# core-ol.net
KiCad netlist of a schematic drawn in EAGLE
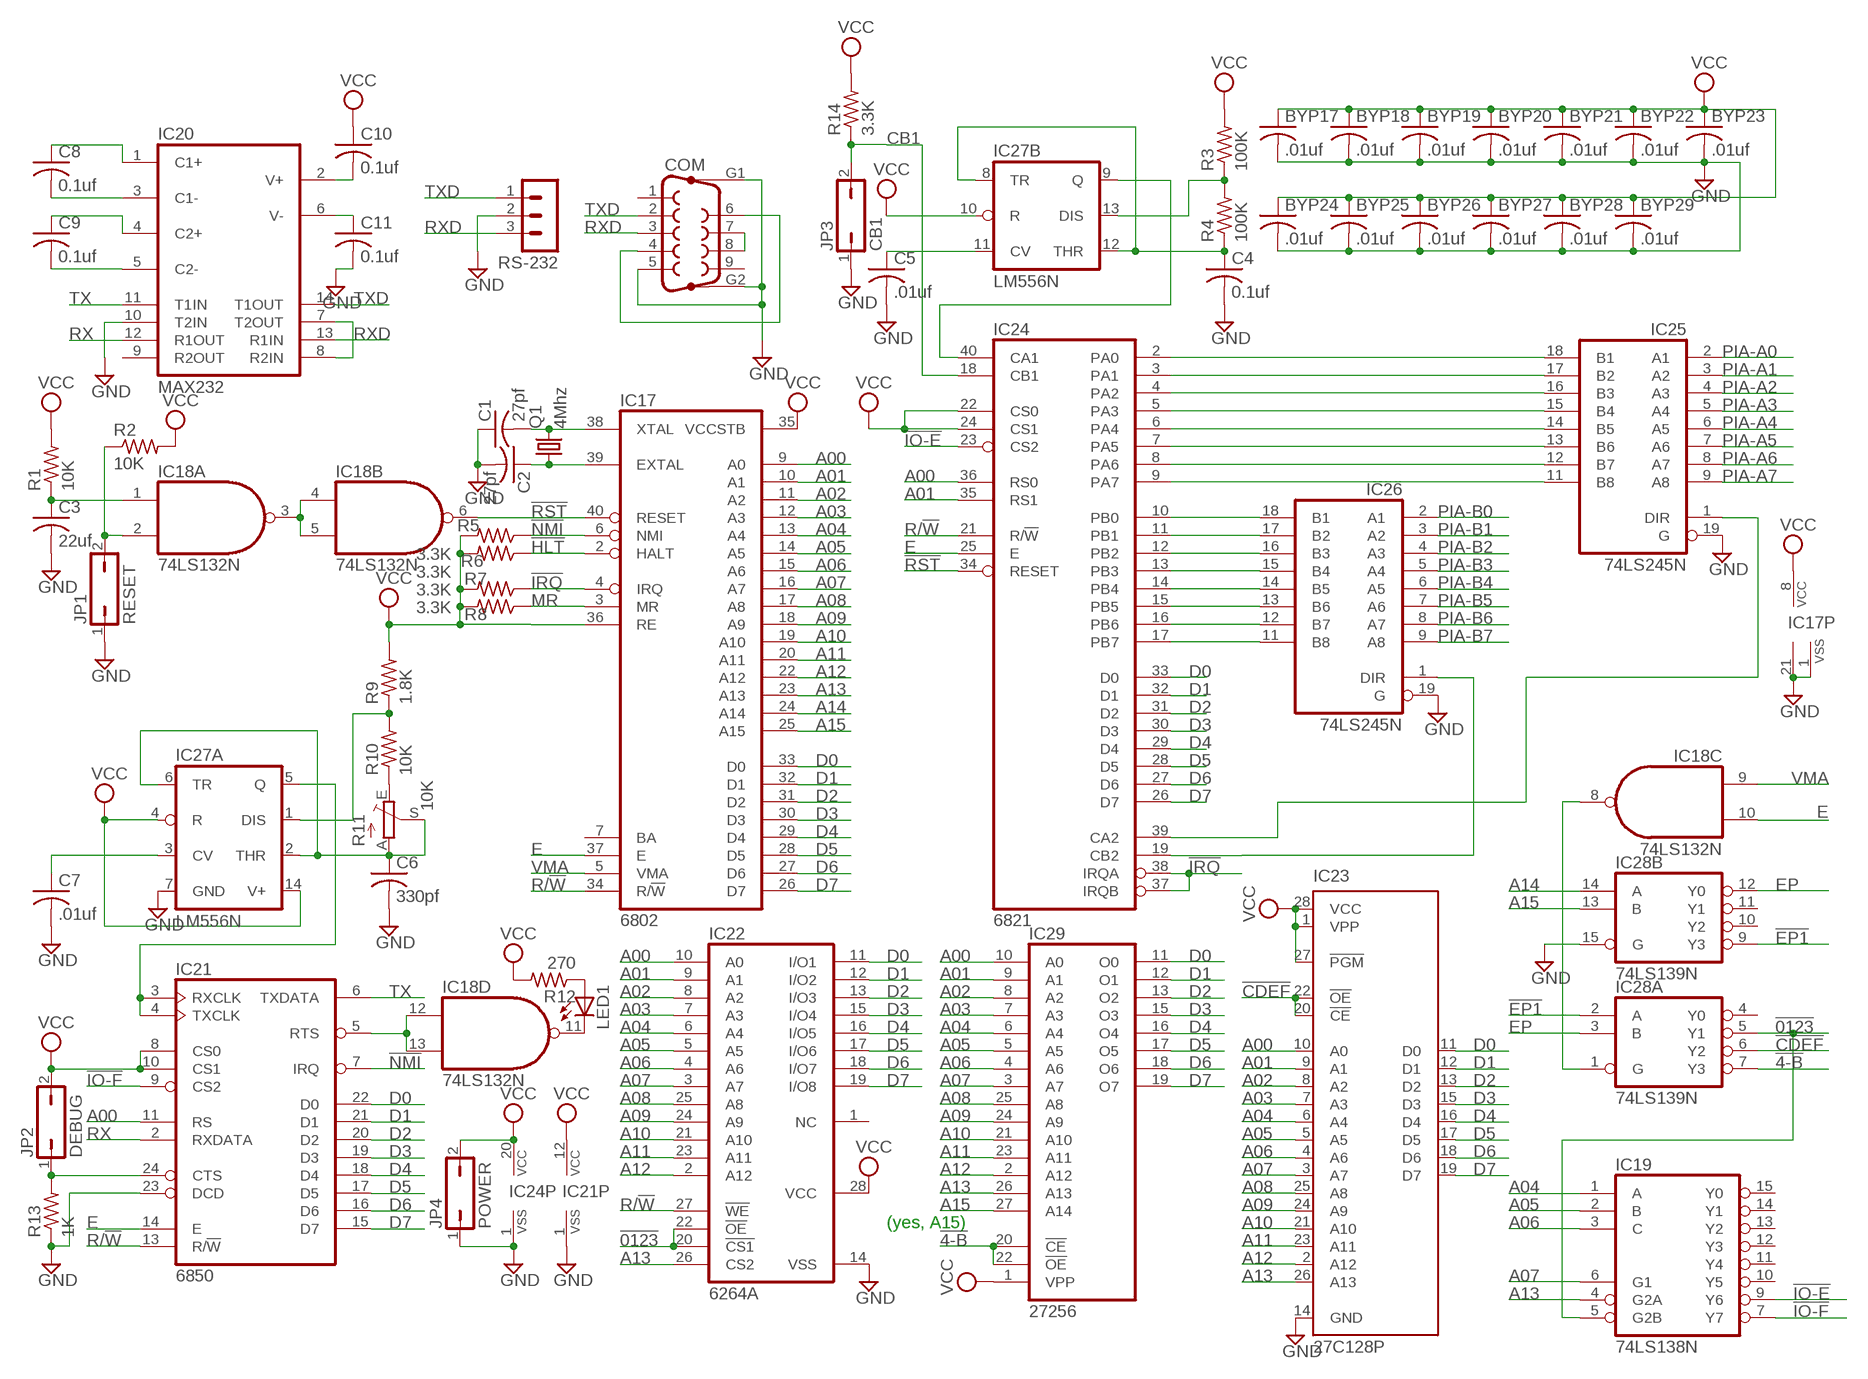
[diagram p0: schematic, sheet 1]
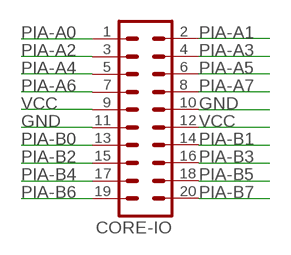
[diagram p1: schematic, sheet 2]

(export (version "E")
  (design (tool "Eeschema 10.0.6"))
  (components
    (comp (ref "BYP17")
      (value ".01uf")
      (footprint "eagle-import:C050-025X075")
      (libsource (lib "eagle-import") (part "C-US050-025X075"))
    )
    (comp (ref "BYP18")
      (value ".01uf")
      (footprint "eagle-import:C050-025X075")
      (libsource (lib "eagle-import") (part "C-US050-025X075"))
    )
    (comp (ref "BYP19")
      (value ".01uf")
      (footprint "eagle-import:C050-025X075")
      (libsource (lib "eagle-import") (part "C-US050-025X075"))
    )
    (comp (ref "BYP20")
      (value ".01uf")
      (footprint "eagle-import:C050-025X075")
      (libsource (lib "eagle-import") (part "C-US050-025X075"))
    )
    (comp (ref "BYP21")
      (value ".01uf")
      (footprint "eagle-import:C050-025X075")
      (libsource (lib "eagle-import") (part "C-US050-025X075"))
    )
    (comp (ref "BYP22")
      (value ".01uf")
      (footprint "eagle-import:C050-025X075")
      (libsource (lib "eagle-import") (part "C-US050-025X075"))
    )
    (comp (ref "BYP23")
      (value ".01uf")
      (footprint "eagle-import:C050-025X075")
      (libsource (lib "eagle-import") (part "C-US050-025X075"))
    )
    (comp (ref "BYP24")
      (value ".01uf")
      (footprint "eagle-import:C050-025X075")
      (libsource (lib "eagle-import") (part "C-US050-025X075"))
    )
    (comp (ref "BYP25")
      (value ".01uf")
      (footprint "eagle-import:C050-025X075")
      (libsource (lib "eagle-import") (part "C-US050-025X075"))
    )
    (comp (ref "BYP26")
      (value ".01uf")
      (footprint "eagle-import:C050-025X075")
      (libsource (lib "eagle-import") (part "C-US050-025X075"))
    )
    (comp (ref "BYP27")
      (value ".01uf")
      (footprint "eagle-import:C050-025X075")
      (libsource (lib "eagle-import") (part "C-US050-025X075"))
    )
    (comp (ref "BYP28")
      (value ".01uf")
      (footprint "eagle-import:C050-025X075")
      (libsource (lib "eagle-import") (part "C-US050-025X075"))
    )
    (comp (ref "BYP29")
      (value ".01uf")
      (footprint "eagle-import:C050-025X075")
      (libsource (lib "eagle-import") (part "C-US050-025X075"))
    )
    (comp (ref "C1")
      (value "27pf")
      (footprint "eagle-import:C050-025X075")
      (libsource (lib "eagle-import") (part "C-US050-025X075"))
    )
    (comp (ref "C2")
      (value "27pf")
      (footprint "eagle-import:C050-025X075")
      (libsource (lib "eagle-import") (part "C-US050-025X075"))
    )
    (comp (ref "C3")
      (value "22uf")
      (footprint "eagle-import:C102-043X133")
      (libsource (lib "eagle-import") (part "C-US102-043X133"))
    )
    (comp (ref "C4")
      (value "0.1uf")
      (footprint "eagle-import:C050-025X075")
      (libsource (lib "eagle-import") (part "C-US050-025X075"))
    )
    (comp (ref "C5")
      (value ".01uf")
      (footprint "eagle-import:C050-025X075")
      (libsource (lib "eagle-import") (part "C-US050-025X075"))
    )
    (comp (ref "C6")
      (value "330pf")
      (footprint "eagle-import:C050-025X075")
      (libsource (lib "eagle-import") (part "C-US050-025X075"))
    )
    (comp (ref "C7")
      (value ".01uf")
      (footprint "eagle-import:C050-025X075")
      (libsource (lib "eagle-import") (part "C-US050-025X075"))
    )
    (comp (ref "C8")
      (value "0.1uf")
      (footprint "eagle-import:C050-025X075")
      (libsource (lib "eagle-import") (part "C-US050-025X075"))
    )
    (comp (ref "C9")
      (value "0.1uf")
      (footprint "eagle-import:C050-025X075")
      (libsource (lib "eagle-import") (part "C-US050-025X075"))
    )
    (comp (ref "C10")
      (value "0.1uf")
      (footprint "eagle-import:C050-025X075")
      (libsource (lib "eagle-import") (part "C-US050-025X075"))
    )
    (comp (ref "C11")
      (value "0.1uf")
      (footprint "eagle-import:C050-025X075")
      (libsource (lib "eagle-import") (part "C-US050-025X075"))
    )
    (comp (ref "COM")
      (value "F09HP")
      (footprint "eagle-import:F09HP")
      (libsource (lib "eagle-import") (part "F09HP"))
    )
    (comp (ref "IC17")
      (value "6802")
      (footprint "eagle-import:DIL40")
      (libsource (lib "eagle-import") (part "6802"))
    )
    (comp (ref "IC18")
      (value "74LS132N")
      (footprint "eagle-import:DIL14")
      (libsource (lib "eagle-import") (part "7400NLS"))
    )
    (comp (ref "IC19")
      (value "74LS138N")
      (footprint "eagle-import:DIL16")
      (libsource (lib "eagle-import") (part "74138NLS"))
    )
    (comp (ref "IC20")
      (value "MAX232")
      (footprint "eagle-import:DIL16")
      (fields (field (name "MF") "MAXIM") (field (name "MPN") "MAX232ACPE+"))
      (libsource (lib "eagle-import") (part "MAX232"))
    )
    (comp (ref "IC21")
      (value "6850")
      (footprint "eagle-import:DIL24")
      (fields (field (name "MF") "NTE ELECTRONICS") (field (name "MPN") "NTE6850"))
      (libsource (lib "eagle-import") (part "6850"))
    )
    (comp (ref "IC22")
      (value "6264A")
      (footprint "eagle-import:DIL28-6")
      (libsource (lib "eagle-import") (part "6264A"))
    )
    (comp (ref "IC23")
      (value "27C128P")
      (footprint "eagle-import:DIL28-6")
      (libsource (lib "eagle-import") (part "27128PC"))
    )
    (comp (ref "IC24")
      (value "6821")
      (footprint "eagle-import:DIL40")
      (fields (field (name "MF") "NTE ELECTRONICS") (field (name "MPN") "NTE6821"))
      (libsource (lib "eagle-import") (part "6821"))
    )
    (comp (ref "IC25")
      (value "74LS245N")
      (footprint "eagle-import:DIL20")
      (libsource (lib "eagle-import") (part "74245NLS"))
    )
    (comp (ref "IC26")
      (value "74LS245N")
      (footprint "eagle-import:DIL20")
      (libsource (lib "eagle-import") (part "74245NLS"))
    )
    (comp (ref "IC27")
      (value "LM556N")
      (footprint "eagle-import:DIL14")
      (libsource (lib "eagle-import") (part "556NLM"))
    )
    (comp (ref "IC28")
      (value "74LS139N")
      (footprint "eagle-import:DIL16")
      (libsource (lib "eagle-import") (part "74139NLS"))
    )
    (comp (ref "IC29")
      (value "27256")
      (footprint "eagle-import:DIL28")
      (libsource (lib "eagle-import") (part "27256"))
    )
    (comp (ref "JP1")
      (value "RESET")
      (footprint "eagle-import:JP1")
      (libsource (lib "eagle-import") (part "JP1Q"))
    )
    (comp (ref "JP2")
      (value "DEBUG")
      (footprint "eagle-import:JP1")
      (libsource (lib "eagle-import") (part "JP1Q"))
    )
    (comp (ref "JP3")
      (value "CB1")
      (footprint "eagle-import:JP1")
      (libsource (lib "eagle-import") (part "JP1Q"))
    )
    (comp (ref "JP4")
      (value "POWER")
      (footprint "eagle-import:JP1")
      (libsource (lib "eagle-import") (part "JP1Q"))
    )
    (comp (ref "LED1")
      (value "LED3MM")
      (footprint "eagle-import:LED3MM")
      (libsource (lib "eagle-import") (part "LED3MM"))
    )
    (comp (ref "Q1")
      (value "4Mhz")
      (footprint "eagle-import:HC18U-V")
      (libsource (lib "eagle-import") (part "CRYSTALHC18U-V"))
    )
    (comp (ref "R1")
      (value "10K")
      (footprint "eagle-import:0207_7")
      (libsource (lib "eagle-import") (part "R-US_0207/7"))
    )
    (comp (ref "R2")
      (value "10K")
      (footprint "eagle-import:0207_7")
      (libsource (lib "eagle-import") (part "R-US_0207/7"))
    )
    (comp (ref "R3")
      (value "100K")
      (footprint "eagle-import:0207_7")
      (libsource (lib "eagle-import") (part "R-US_0207/7"))
    )
    (comp (ref "R4")
      (value "100K")
      (footprint "eagle-import:0207_7")
      (libsource (lib "eagle-import") (part "R-US_0207/7"))
    )
    (comp (ref "R5")
      (value "3.3K")
      (footprint "eagle-import:0207_7")
      (libsource (lib "eagle-import") (part "R-US_0207/7"))
    )
    (comp (ref "R6")
      (value "3.3K")
      (footprint "eagle-import:0207_7")
      (libsource (lib "eagle-import") (part "R-US_0207/7"))
    )
    (comp (ref "R7")
      (value "3.3K")
      (footprint "eagle-import:0207_7")
      (libsource (lib "eagle-import") (part "R-US_0207/7"))
    )
    (comp (ref "R8")
      (value "3.3K")
      (footprint "eagle-import:0207_7")
      (libsource (lib "eagle-import") (part "R-US_0207/7"))
    )
    (comp (ref "R9")
      (value "1.8K")
      (footprint "eagle-import:0207_7")
      (libsource (lib "eagle-import") (part "R-US_0207/7"))
    )
    (comp (ref "R10")
      (value "10K")
      (footprint "eagle-import:0207_7")
      (libsource (lib "eagle-import") (part "R-US_0207/7"))
    )
    (comp (ref "R11")
      (value "10K")
      (footprint "eagle-import:SP19L")
      (libsource (lib "eagle-import") (part "TRIM_EU-B90P"))
    )
    (comp (ref "R12")
      (value "270")
      (footprint "eagle-import:0207_7")
      (libsource (lib "eagle-import") (part "R-US_0207/7"))
    )
    (comp (ref "R13")
      (value "1K")
      (footprint "eagle-import:0207_7")
      (libsource (lib "eagle-import") (part "R-US_0207/7"))
    )
    (comp (ref "R14")
      (value "3.3K")
      (footprint "eagle-import:0207_7")
      (libsource (lib "eagle-import") (part "R-US_0207/7"))
    )
    (comp (ref "RS-232")
      (value "MA03-1")
      (footprint "eagle-import:MA03-1")
      (libsource (lib "eagle-import") (part "MA03-1"))
    )
    (comp (ref "CORE-IO")
      (value "MA10-2")
      (footprint "eagle-import:MA10-2")
      (libsource (lib "eagle-import") (part "MA10-2"))
    )
  )
  (nets
    (net (code "1") (name "A00") (class "Default")
      (node (ref "IC17") (pin "9") (pinfunction "A0_9") (pintype "output"))
      (node (ref "IC21") (pin "11") (pinfunction "RS_11") (pintype "input"))
      (node (ref "IC22") (pin "10") (pinfunction "A0_10") (pintype "input"))
      (node (ref "IC23") (pin "10") (pinfunction "A0_10") (pintype "input"))
      (node (ref "IC24") (pin "36") (pinfunction "RS0_36") (pintype "input"))
      (node (ref "IC29") (pin "10") (pinfunction "A0_10") (pintype "input"))
    )
    (net (code "2") (name "A01") (class "Default")
      (node (ref "IC17") (pin "10") (pinfunction "A1_10") (pintype "output"))
      (node (ref "IC22") (pin "9") (pinfunction "A1_9") (pintype "input"))
      (node (ref "IC23") (pin "9") (pinfunction "A1_9") (pintype "input"))
      (node (ref "IC24") (pin "35") (pinfunction "RS1_35") (pintype "input"))
      (node (ref "IC29") (pin "9") (pinfunction "A1_9") (pintype "input"))
    )
    (net (code "3") (name "A02") (class "Default")
      (node (ref "IC17") (pin "11") (pinfunction "A2_11") (pintype "output"))
      (node (ref "IC22") (pin "8") (pinfunction "A2_8") (pintype "input"))
      (node (ref "IC23") (pin "8") (pinfunction "A2_8") (pintype "input"))
      (node (ref "IC29") (pin "8") (pinfunction "A2_8") (pintype "input"))
    )
    (net (code "4") (name "A03") (class "Default")
      (node (ref "IC17") (pin "12") (pinfunction "A3_12") (pintype "output"))
      (node (ref "IC22") (pin "7") (pinfunction "A3_7") (pintype "input"))
      (node (ref "IC23") (pin "7") (pinfunction "A3_7") (pintype "input"))
      (node (ref "IC29") (pin "7") (pinfunction "A3_7") (pintype "input"))
    )
    (net (code "5") (name "A04") (class "Default")
      (node (ref "IC17") (pin "13") (pinfunction "A4_13") (pintype "output"))
      (node (ref "IC19") (pin "1") (pinfunction "A_1") (pintype "input"))
      (node (ref "IC22") (pin "6") (pinfunction "A4_6") (pintype "input"))
      (node (ref "IC23") (pin "6") (pinfunction "A4_6") (pintype "input"))
      (node (ref "IC29") (pin "6") (pinfunction "A4_6") (pintype "input"))
    )
    (net (code "6") (name "A05") (class "Default")
      (node (ref "IC17") (pin "14") (pinfunction "A5_14") (pintype "output"))
      (node (ref "IC19") (pin "2") (pinfunction "B_2") (pintype "input"))
      (node (ref "IC22") (pin "5") (pinfunction "A5_5") (pintype "input"))
      (node (ref "IC23") (pin "5") (pinfunction "A5_5") (pintype "input"))
      (node (ref "IC29") (pin "5") (pinfunction "A5_5") (pintype "input"))
    )
    (net (code "7") (name "A06") (class "Default")
      (node (ref "IC17") (pin "15") (pinfunction "A6_15") (pintype "output"))
      (node (ref "IC19") (pin "3") (pinfunction "C_3") (pintype "input"))
      (node (ref "IC22") (pin "4") (pinfunction "A6_4") (pintype "input"))
      (node (ref "IC23") (pin "4") (pinfunction "A6_4") (pintype "input"))
      (node (ref "IC29") (pin "4") (pinfunction "A6_4") (pintype "input"))
    )
    (net (code "8") (name "A07") (class "Default")
      (node (ref "IC17") (pin "16") (pinfunction "A7_16") (pintype "output"))
      (node (ref "IC19") (pin "6") (pinfunction "G1_6") (pintype "input"))
      (node (ref "IC22") (pin "3") (pinfunction "A7_3") (pintype "input"))
      (node (ref "IC23") (pin "3") (pinfunction "A7_3") (pintype "input"))
      (node (ref "IC29") (pin "3") (pinfunction "A7_3") (pintype "input"))
    )
    (net (code "9") (name "A08") (class "Default")
      (node (ref "IC17") (pin "17") (pinfunction "A8_17") (pintype "output"))
      (node (ref "IC22") (pin "25") (pinfunction "A8_25") (pintype "input"))
      (node (ref "IC23") (pin "25") (pinfunction "A8_25") (pintype "input"))
      (node (ref "IC29") (pin "25") (pinfunction "A8_25") (pintype "input"))
    )
    (net (code "10") (name "A09") (class "Default")
      (node (ref "IC17") (pin "18") (pinfunction "A9_18") (pintype "output"))
      (node (ref "IC22") (pin "24") (pinfunction "A9_24") (pintype "input"))
      (node (ref "IC23") (pin "24") (pinfunction "A9_24") (pintype "input"))
      (node (ref "IC29") (pin "24") (pinfunction "A9_24") (pintype "input"))
    )
    (net (code "11") (name "A10") (class "Default")
      (node (ref "IC17") (pin "19") (pinfunction "A10_19") (pintype "output"))
      (node (ref "IC22") (pin "21") (pinfunction "A10_21") (pintype "input"))
      (node (ref "IC23") (pin "21") (pinfunction "A10_21") (pintype "input"))
      (node (ref "IC29") (pin "21") (pinfunction "A10_21") (pintype "input"))
    )
    (net (code "12") (name "A11") (class "Default")
      (node (ref "IC17") (pin "20") (pinfunction "A11_20") (pintype "output"))
      (node (ref "IC22") (pin "23") (pinfunction "A11_23") (pintype "input"))
      (node (ref "IC23") (pin "23") (pinfunction "A11_23") (pintype "input"))
      (node (ref "IC29") (pin "23") (pinfunction "A11_23") (pintype "input"))
    )
    (net (code "13") (name "A12") (class "Default")
      (node (ref "IC17") (pin "22") (pinfunction "A12_22") (pintype "output"))
      (node (ref "IC22") (pin "2") (pinfunction "A12_2") (pintype "input"))
      (node (ref "IC23") (pin "2") (pinfunction "A12_2") (pintype "input"))
      (node (ref "IC29") (pin "2") (pinfunction "A12_2") (pintype "input"))
    )
    (net (code "14") (name "A13") (class "Default")
      (node (ref "IC17") (pin "23") (pinfunction "A13_23") (pintype "output"))
      (node (ref "IC19") (pin "4") (pinfunction "G2A_4") (pintype "input"))
      (node (ref "IC22") (pin "26") (pinfunction "CS2_26") (pintype "input"))
      (node (ref "IC23") (pin "26") (pinfunction "A13_26") (pintype "input"))
      (node (ref "IC29") (pin "26") (pinfunction "A13_26") (pintype "input"))
    )
    (net (code "15") (name "A14") (class "Default")
      (node (ref "IC17") (pin "24") (pinfunction "A14_24") (pintype "output"))
      (node (ref "IC28") (pin "14") (pinfunction "A_14") (pintype "input"))
    )
    (net (code "16") (name "A15") (class "Default")
      (node (ref "IC17") (pin "25") (pinfunction "A15_25") (pintype "output"))
      (node (ref "IC28") (pin "13") (pinfunction "B_13") (pintype "input"))
      (node (ref "IC29") (pin "27") (pinfunction "A14_27") (pintype "input"))
    )
    (net (code "17") (name "CB1") (class "Default")
      (node (ref "IC24") (pin "18") (pinfunction "CB1_18") (pintype "input"))
      (node (ref "JP3") (pin "2") (pinfunction "2_2") (pintype "passive"))
      (node (ref "R14") (pin "1") (pinfunction "1_1") (pintype "passive"))
    )
    (net (code "18") (name "D0") (class "Default")
      (node (ref "IC17") (pin "33") (pinfunction "D0_33") (pintype "bidirectional"))
      (node (ref "IC21") (pin "22") (pinfunction "D0_22") (pintype "bidirectional"))
      (node (ref "IC22") (pin "11") (pinfunction "I/O1_11") (pintype "bidirectional"))
      (node (ref "IC23") (pin "11") (pinfunction "D0_11") (pintype "tri_state"))
      (node (ref "IC24") (pin "33") (pinfunction "D0_33") (pintype "bidirectional"))
      (node (ref "IC29") (pin "11") (pinfunction "O0_11") (pintype "tri_state"))
    )
    (net (code "19") (name "D1") (class "Default")
      (node (ref "IC17") (pin "32") (pinfunction "D1_32") (pintype "bidirectional"))
      (node (ref "IC21") (pin "21") (pinfunction "D1_21") (pintype "bidirectional"))
      (node (ref "IC22") (pin "12") (pinfunction "I/O2_12") (pintype "bidirectional"))
      (node (ref "IC23") (pin "12") (pinfunction "D1_12") (pintype "tri_state"))
      (node (ref "IC24") (pin "32") (pinfunction "D1_32") (pintype "bidirectional"))
      (node (ref "IC29") (pin "12") (pinfunction "O1_12") (pintype "tri_state"))
    )
    (net (code "20") (name "D2") (class "Default")
      (node (ref "IC17") (pin "31") (pinfunction "D2_31") (pintype "bidirectional"))
      (node (ref "IC21") (pin "20") (pinfunction "D2_20") (pintype "bidirectional"))
      (node (ref "IC22") (pin "13") (pinfunction "I/O3_13") (pintype "bidirectional"))
      (node (ref "IC23") (pin "13") (pinfunction "D2_13") (pintype "tri_state"))
      (node (ref "IC24") (pin "31") (pinfunction "D2_31") (pintype "bidirectional"))
      (node (ref "IC29") (pin "13") (pinfunction "O2_13") (pintype "tri_state"))
    )
    (net (code "21") (name "D3") (class "Default")
      (node (ref "IC17") (pin "30") (pinfunction "D3_30") (pintype "bidirectional"))
      (node (ref "IC21") (pin "19") (pinfunction "D3_19") (pintype "bidirectional"))
      (node (ref "IC22") (pin "15") (pinfunction "I/O4_15") (pintype "bidirectional"))
      (node (ref "IC23") (pin "15") (pinfunction "D3_15") (pintype "tri_state"))
      (node (ref "IC24") (pin "30") (pinfunction "D3_30") (pintype "bidirectional"))
      (node (ref "IC29") (pin "15") (pinfunction "O3_15") (pintype "tri_state"))
    )
    (net (code "22") (name "D4") (class "Default")
      (node (ref "IC17") (pin "29") (pinfunction "D4_29") (pintype "bidirectional"))
      (node (ref "IC21") (pin "18") (pinfunction "D4_18") (pintype "bidirectional"))
      (node (ref "IC22") (pin "16") (pinfunction "I/O5_16") (pintype "bidirectional"))
      (node (ref "IC23") (pin "16") (pinfunction "D4_16") (pintype "tri_state"))
      (node (ref "IC24") (pin "29") (pinfunction "D4_29") (pintype "bidirectional"))
      (node (ref "IC29") (pin "16") (pinfunction "O4_16") (pintype "tri_state"))
    )
    (net (code "23") (name "D5") (class "Default")
      (node (ref "IC17") (pin "28") (pinfunction "D5_28") (pintype "bidirectional"))
      (node (ref "IC21") (pin "17") (pinfunction "D5_17") (pintype "bidirectional"))
      (node (ref "IC22") (pin "17") (pinfunction "I/O6_17") (pintype "bidirectional"))
      (node (ref "IC23") (pin "17") (pinfunction "D5_17") (pintype "tri_state"))
      (node (ref "IC24") (pin "28") (pinfunction "D5_28") (pintype "bidirectional"))
      (node (ref "IC29") (pin "17") (pinfunction "O5_17") (pintype "tri_state"))
    )
    (net (code "24") (name "D6") (class "Default")
      (node (ref "IC17") (pin "27") (pinfunction "D6_27") (pintype "bidirectional"))
      (node (ref "IC21") (pin "16") (pinfunction "D6_16") (pintype "bidirectional"))
      (node (ref "IC22") (pin "18") (pinfunction "I/O7_18") (pintype "bidirectional"))
      (node (ref "IC23") (pin "18") (pinfunction "D6_18") (pintype "tri_state"))
      (node (ref "IC24") (pin "27") (pinfunction "D6_27") (pintype "bidirectional"))
      (node (ref "IC29") (pin "18") (pinfunction "O6_18") (pintype "tri_state"))
    )
    (net (code "25") (name "D7") (class "Default")
      (node (ref "IC17") (pin "26") (pinfunction "D7_26") (pintype "bidirectional"))
      (node (ref "IC21") (pin "15") (pinfunction "D7_15") (pintype "bidirectional"))
      (node (ref "IC22") (pin "19") (pinfunction "I/O8_19") (pintype "bidirectional"))
      (node (ref "IC23") (pin "19") (pinfunction "D7_19") (pintype "tri_state"))
      (node (ref "IC24") (pin "26") (pinfunction "D7_26") (pintype "bidirectional"))
      (node (ref "IC29") (pin "19") (pinfunction "O7_19") (pintype "tri_state"))
    )
    (net (code "26") (name "E") (class "Default")
      (node (ref "IC17") (pin "37") (pinfunction "E_37") (pintype "output"))
      (node (ref "IC18") (pin "10") (pinfunction "I1_10") (pintype "input"))
      (node (ref "IC21") (pin "14") (pinfunction "E_14") (pintype "input"))
      (node (ref "IC24") (pin "25") (pinfunction "E_25") (pintype "input"))
    )
    (net (code "27") (name "EP") (class "Default")
      (node (ref "IC28") (pin "12") (pinfunction "Y0_12") (pintype "output"))
      (node (ref "IC28") (pin "3") (pinfunction "B_3") (pintype "input"))
    )
    (net (code "28") (name "GND") (class "Default")
      (node (ref "BYP17") (pin "2") (pinfunction "2_2") (pintype "passive"))
      (node (ref "BYP18") (pin "2") (pinfunction "2_2") (pintype "passive"))
      (node (ref "BYP19") (pin "2") (pinfunction "2_2") (pintype "passive"))
      (node (ref "BYP20") (pin "2") (pinfunction "2_2") (pintype "passive"))
      (node (ref "BYP21") (pin "2") (pinfunction "2_2") (pintype "passive"))
      (node (ref "BYP22") (pin "2") (pinfunction "2_2") (pintype "passive"))
      (node (ref "BYP23") (pin "2") (pinfunction "2_2") (pintype "passive"))
      (node (ref "BYP24") (pin "2") (pinfunction "2_2") (pintype "passive"))
      (node (ref "BYP25") (pin "2") (pinfunction "2_2") (pintype "passive"))
      (node (ref "BYP26") (pin "2") (pinfunction "2_2") (pintype "passive"))
      (node (ref "BYP27") (pin "2") (pinfunction "2_2") (pintype "passive"))
      (node (ref "BYP28") (pin "2") (pinfunction "2_2") (pintype "passive"))
      (node (ref "BYP29") (pin "2") (pinfunction "2_2") (pintype "passive"))
      (node (ref "C1") (pin "1") (pinfunction "1_1") (pintype "passive"))
      (node (ref "C11") (pin "2") (pinfunction "2_2") (pintype "passive"))
      (node (ref "C2") (pin "2") (pinfunction "2_2") (pintype "passive"))
      (node (ref "C3") (pin "2") (pinfunction "2_2") (pintype "passive"))
      (node (ref "C4") (pin "2") (pinfunction "2_2") (pintype "passive"))
      (node (ref "C5") (pin "2") (pinfunction "2_2") (pintype "passive"))
      (node (ref "C6") (pin "2") (pinfunction "2_2") (pintype "passive"))
      (node (ref "C7") (pin "2") (pinfunction "2_2") (pintype "passive"))
      (node (ref "COM") (pin "5") (pinfunction "5_5") (pintype "passive"))
      (node (ref "COM") (pin "G1") (pinfunction "G1_G1") (pintype "passive"))
      (node (ref "COM") (pin "G2") (pinfunction "G2_G2") (pintype "passive"))
      (node (ref "CORE-IO") (pin "10") (pinfunction "10_10") (pintype "passive"))
      (node (ref "CORE-IO") (pin "11") (pinfunction "11_11") (pintype "passive"))
      (node (ref "IC17") (pin "1") (pinfunction "VSS_1") (pintype "power_in"))
      (node (ref "IC17") (pin "21") (pinfunction "VSS_21") (pintype "power_in"))
      (node (ref "IC20") (pin "10") (pinfunction "T2IN_10") (pintype "input"))
      (node (ref "IC21") (pin "1") (pinfunction "VSS_1") (pintype "power_in"))
      (node (ref "IC21") (pin "23") (pinfunction "DCD_23") (pintype "input"))
      (node (ref "IC22") (pin "14") (pinfunction "VSS_14") (pintype "power_in"))
      (node (ref "IC23") (pin "14") (pinfunction "GND_14") (pintype "power_in"))
      (node (ref "IC24") (pin "1") (pinfunction "VSS_1") (pintype "power_in"))
      (node (ref "IC25") (pin "19") (pinfunction "G_19") (pintype "input"))
      (node (ref "IC26") (pin "19") (pinfunction "G_19") (pintype "input"))
      (node (ref "IC27") (pin "7") (pinfunction "GND_7") (pintype "power_in"))
      (node (ref "IC28") (pin "15") (pinfunction "G_15") (pintype "input"))
      (node (ref "JP1") (pin "1") (pinfunction "1_1") (pintype "passive"))
      (node (ref "JP3") (pin "1") (pinfunction "1_1") (pintype "passive"))
      (node (ref "JP4") (pin "1") (pinfunction "1_1") (pintype "passive"))
      (node (ref "R13") (pin "1") (pinfunction "1_1") (pintype "passive"))
      (node (ref "RS-232") (pin "2") (pinfunction "2_2") (pintype "passive"))
    )
    (net (code "29") (name "MR") (class "Default")
      (node (ref "IC17") (pin "3") (pinfunction "MR_3") (pintype "input"))
      (node (ref "R8") (pin "1") (pinfunction "1_1") (pintype "passive"))
    )
    (net (code "30") (name "Net-(COM-Pad4)") (class "Default")
      (node (ref "COM") (pin "4") (pinfunction "4_4") (pintype "passive"))
      (node (ref "COM") (pin "6") (pinfunction "6_6") (pintype "passive"))
    )
    (net (code "31") (name "Net-(COM-Pad7)") (class "Default")
      (node (ref "COM") (pin "7") (pinfunction "7_7") (pintype "passive"))
      (node (ref "COM") (pin "8") (pinfunction "8_8") (pintype "passive"))
    )
    (net (code "32") (name "Net-(IC17A-EXTAL)") (class "Default")
      (node (ref "C2") (pin "1") (pinfunction "1_1") (pintype "passive"))
      (node (ref "IC17") (pin "39") (pinfunction "EXTAL_39") (pintype "input"))
      (node (ref "Q1") (pin "1") (pinfunction "1_1") (pintype "passive"))
    )
    (net (code "33") (name "Net-(IC17A-XTAL)") (class "Default")
      (node (ref "C1") (pin "2") (pinfunction "2_2") (pintype "passive"))
      (node (ref "IC17") (pin "38") (pinfunction "XTAL_38") (pintype "input"))
      (node (ref "Q1") (pin "2") (pinfunction "2_2") (pintype "passive"))
    )
    (net (code "34") (name "Net-(IC18A-I0)") (class "Default")
      (node (ref "C3") (pin "1") (pinfunction "1_1") (pintype "passive"))
      (node (ref "IC18") (pin "1") (pinfunction "I0_1") (pintype "input"))
      (node (ref "R1") (pin "1") (pinfunction "1_1") (pintype "passive"))
    )
    (net (code "35") (name "Net-(IC18A-I1)") (class "Default")
      (node (ref "IC18") (pin "2") (pinfunction "I1_2") (pintype "input"))
      (node (ref "JP1") (pin "2") (pinfunction "2_2") (pintype "passive"))
      (node (ref "R2") (pin "1") (pinfunction "1_1") (pintype "passive"))
    )
    (net (code "36") (name "Net-(IC18A-O)") (class "Default")
      (node (ref "IC18") (pin "3") (pinfunction "O_3") (pintype "output"))
      (node (ref "IC18") (pin "4") (pinfunction "I0_4") (pintype "input"))
      (node (ref "IC18") (pin "5") (pinfunction "I1_5") (pintype "input"))
    )
    (net (code "37") (name "Net-(IC18C-O)") (class "Default")
      (node (ref "IC18") (pin "8") (pinfunction "O_8") (pintype "output"))
      (node (ref "IC28") (pin "1") (pinfunction "G_1") (pintype "input"))
    )
    (net (code "38") (name "Net-(IC18D-I0)") (class "Default")
      (node (ref "IC18") (pin "12") (pinfunction "I0_12") (pintype "input"))
      (node (ref "IC18") (pin "13") (pinfunction "I1_13") (pintype "input"))
      (node (ref "IC21") (pin "5") (pinfunction "RTS_5") (pintype "output"))
    )
    (net (code "39") (name "Net-(IC18D-O)") (class "Default")
      (node (ref "IC18") (pin "11") (pinfunction "O_11") (pintype "output"))
      (node (ref "LED1") (pin "K") (pinfunction "C_K") (pintype "passive"))
    )
    (net (code "40") (name "Net-(IC20A-C1+)") (class "Default")
      (node (ref "C8") (pin "1") (pinfunction "1_1") (pintype "passive"))
      (node (ref "IC20") (pin "1") (pinfunction "C1+_1") (pintype "bidirectional"))
    )
    (net (code "41") (name "Net-(IC20A-C1-)") (class "Default")
      (node (ref "C8") (pin "2") (pinfunction "2_2") (pintype "passive"))
      (node (ref "IC20") (pin "3") (pinfunction "C1-_3") (pintype "bidirectional"))
    )
    (net (code "42") (name "Net-(IC20A-C2+)") (class "Default")
      (node (ref "C9") (pin "1") (pinfunction "1_1") (pintype "passive"))
      (node (ref "IC20") (pin "4") (pinfunction "C2+_4") (pintype "bidirectional"))
    )
    (net (code "43") (name "Net-(IC20A-C2-)") (class "Default")
      (node (ref "C9") (pin "2") (pinfunction "2_2") (pintype "passive"))
      (node (ref "IC20") (pin "5") (pinfunction "C2-_5") (pintype "bidirectional"))
    )
    (net (code "44") (name "Net-(IC20A-R2IN)") (class "Default")
      (node (ref "IC20") (pin "7") (pinfunction "T2OUT_7") (pintype "output"))
      (node (ref "IC20") (pin "8") (pinfunction "R2IN_8") (pintype "input"))
    )
    (net (code "45") (name "Net-(IC20A-V+)") (class "Default")
      (node (ref "C10") (pin "2") (pinfunction "2_2") (pintype "passive"))
      (node (ref "IC20") (pin "2") (pinfunction "V+_2") (pintype "bidirectional"))
    )
    (net (code "46") (name "Net-(IC20A-V-)") (class "Default")
      (node (ref "C11") (pin "1") (pinfunction "1_1") (pintype "passive"))
      (node (ref "IC20") (pin "6") (pinfunction "V-_6") (pintype "bidirectional"))
    )
    (net (code "47") (name "Net-(IC21A-CTS)") (class "Default")
      (node (ref "IC21") (pin "24") (pinfunction "CTS_24") (pintype "input"))
      (node (ref "JP2") (pin "1") (pinfunction "1_1") (pintype "passive"))
      (node (ref "R13") (pin "2") (pinfunction "2_2") (pintype "passive"))
    )
    (net (code "48") (name "Net-(IC21A-RXCLK)") (class "Default")
      (node (ref "IC21") (pin "3") (pinfunction "RXCLK_3") (pintype "input"))
      (node (ref "IC21") (pin "4") (pinfunction "TXCLK_4") (pintype "input"))
      (node (ref "IC27") (pin "5") (pinfunction "Q_5") (pintype "output"))
    )
    (net (code "49") (name "Net-(IC24A-CA1)") (class "Default")
      (node (ref "IC24") (pin "40") (pinfunction "CA1_40") (pintype "input"))
      (node (ref "IC27") (pin "9") (pinfunction "Q_9") (pintype "output"))
    )
    (net (code "50") (name "Net-(IC24A-CA2)") (class "Default")
      (node (ref "IC24") (pin "39") (pinfunction "CA2_39") (pintype "bidirectional"))
      (node (ref "IC25") (pin "1") (pinfunction "DIR_1") (pintype "input"))
    )
    (net (code "51") (name "Net-(IC24A-CB2)") (class "Default")
      (node (ref "IC24") (pin "19") (pinfunction "CB2_19") (pintype "bidirectional"))
      (node (ref "IC26") (pin "1") (pinfunction "DIR_1") (pintype "input"))
    )
    (net (code "52") (name "Net-(IC24A-PA0)") (class "Default")
      (node (ref "IC24") (pin "2") (pinfunction "PA0_2") (pintype "bidirectional"))
      (node (ref "IC25") (pin "18") (pinfunction "B1_18") (pintype "bidirectional"))
    )
    (net (code "53") (name "Net-(IC24A-PA1)") (class "Default")
      (node (ref "IC24") (pin "3") (pinfunction "PA1_3") (pintype "bidirectional"))
      (node (ref "IC25") (pin "17") (pinfunction "B2_17") (pintype "bidirectional"))
    )
    (net (code "54") (name "Net-(IC24A-PA2)") (class "Default")
      (node (ref "IC24") (pin "4") (pinfunction "PA2_4") (pintype "bidirectional"))
      (node (ref "IC25") (pin "16") (pinfunction "B3_16") (pintype "bidirectional"))
    )
    (net (code "55") (name "Net-(IC24A-PA3)") (class "Default")
      (node (ref "IC24") (pin "5") (pinfunction "PA3_5") (pintype "bidirectional"))
      (node (ref "IC25") (pin "15") (pinfunction "B4_15") (pintype "bidirectional"))
    )
    (net (code "56") (name "Net-(IC24A-PA4)") (class "Default")
      (node (ref "IC24") (pin "6") (pinfunction "PA4_6") (pintype "bidirectional"))
      (node (ref "IC25") (pin "14") (pinfunction "B5_14") (pintype "bidirectional"))
    )
    (net (code "57") (name "Net-(IC24A-PA5)") (class "Default")
      (node (ref "IC24") (pin "7") (pinfunction "PA5_7") (pintype "bidirectional"))
      (node (ref "IC25") (pin "13") (pinfunction "B6_13") (pintype "bidirectional"))
    )
    (net (code "58") (name "Net-(IC24A-PA6)") (class "Default")
      (node (ref "IC24") (pin "8") (pinfunction "PA6_8") (pintype "bidirectional"))
      (node (ref "IC25") (pin "12") (pinfunction "B7_12") (pintype "bidirectional"))
    )
    (net (code "59") (name "Net-(IC24A-PA7)") (class "Default")
      (node (ref "IC24") (pin "9") (pinfunction "PA7_9") (pintype "bidirectional"))
      (node (ref "IC25") (pin "11") (pinfunction "B8_11") (pintype "bidirectional"))
    )
    (net (code "60") (name "Net-(IC24A-PB0)") (class "Default")
      (node (ref "IC24") (pin "10") (pinfunction "PB0_10") (pintype "bidirectional"))
      (node (ref "IC26") (pin "18") (pinfunction "B1_18") (pintype "bidirectional"))
    )
    (net (code "61") (name "Net-(IC24A-PB1)") (class "Default")
      (node (ref "IC24") (pin "11") (pinfunction "PB1_11") (pintype "bidirectional"))
      (node (ref "IC26") (pin "17") (pinfunction "B2_17") (pintype "bidirectional"))
    )
    (net (code "62") (name "Net-(IC24A-PB2)") (class "Default")
      (node (ref "IC24") (pin "12") (pinfunction "PB2_12") (pintype "bidirectional"))
      (node (ref "IC26") (pin "16") (pinfunction "B3_16") (pintype "bidirectional"))
    )
    (net (code "63") (name "Net-(IC24A-PB3)") (class "Default")
      (node (ref "IC24") (pin "13") (pinfunction "PB3_13") (pintype "bidirectional"))
      (node (ref "IC26") (pin "15") (pinfunction "B4_15") (pintype "bidirectional"))
    )
    (net (code "64") (name "Net-(IC24A-PB4)") (class "Default")
      (node (ref "IC24") (pin "14") (pinfunction "PB4_14") (pintype "bidirectional"))
      (node (ref "IC26") (pin "14") (pinfunction "B5_14") (pintype "bidirectional"))
    )
    (net (code "65") (name "Net-(IC24A-PB5)") (class "Default")
      (node (ref "IC24") (pin "15") (pinfunction "PB5_15") (pintype "bidirectional"))
      (node (ref "IC26") (pin "13") (pinfunction "B6_13") (pintype "bidirectional"))
    )
    (net (code "66") (name "Net-(IC24A-PB6)") (class "Default")
      (node (ref "IC24") (pin "16") (pinfunction "PB6_16") (pintype "bidirectional"))
      (node (ref "IC26") (pin "12") (pinfunction "B7_12") (pintype "bidirectional"))
    )
    (net (code "67") (name "Net-(IC24A-PB7)") (class "Default")
      (node (ref "IC24") (pin "17") (pinfunction "PB7_17") (pintype "bidirectional"))
      (node (ref "IC26") (pin "11") (pinfunction "B8_11") (pintype "bidirectional"))
    )
    (net (code "68") (name "Net-(IC27A-CV)") (class "Default")
      (node (ref "C7") (pin "1") (pinfunction "1_1") (pintype "passive"))
      (node (ref "IC27") (pin "3") (pinfunction "CV_3") (pintype "input"))
    )
    (net (code "69") (name "Net-(IC27A-DIS)") (class "Default")
      (node (ref "IC27") (pin "1") (pinfunction "DIS_1") (pintype "input"))
      (node (ref "R10") (pin "2") (pinfunction "2_2") (pintype "passive"))
      (node (ref "R9") (pin "1") (pinfunction "1_1") (pintype "passive"))
    )
    (net (code "70") (name "Net-(IC27A-THR)") (class "Default")
      (node (ref "C6") (pin "1") (pinfunction "1_1") (pintype "passive"))
      (node (ref "IC27") (pin "2") (pinfunction "THR_2") (pintype "input"))
      (node (ref "IC27") (pin "6") (pinfunction "TR_6") (pintype "input"))
      (node (ref "R11") (pin "A") (pinfunction "A_A") (pintype "passive"))
      (node (ref "R11") (pin "S") (pinfunction "S_S") (pintype "passive"))
    )
    (net (code "71") (name "Net-(IC27B-CV)") (class "Default")
      (node (ref "C5") (pin "1") (pinfunction "1_1") (pintype "passive"))
      (node (ref "IC27") (pin "11") (pinfunction "CV_11") (pintype "input"))
    )
    (net (code "72") (name "Net-(IC27B-DIS)") (class "Default")
      (node (ref "IC27") (pin "13") (pinfunction "DIS_13") (pintype "input"))
      (node (ref "R3") (pin "1") (pinfunction "1_1") (pintype "passive"))
      (node (ref "R4") (pin "2") (pinfunction "2_2") (pintype "passive"))
    )
    (net (code "73") (name "Net-(IC27B-THR)") (class "Default")
      (node (ref "C4") (pin "1") (pinfunction "1_1") (pintype "passive"))
      (node (ref "IC27") (pin "12") (pinfunction "THR_12") (pintype "input"))
      (node (ref "IC27") (pin "8") (pinfunction "TR_8") (pintype "input"))
      (node (ref "R4") (pin "1") (pinfunction "1_1") (pintype "passive"))
    )
    (net (code "74") (name "Net-(LED1-PadA)") (class "Default")
      (node (ref "LED1") (pin "A") (pinfunction "A_A") (pintype "passive"))
      (node (ref "R12") (pin "1") (pinfunction "1_1") (pintype "passive"))
    )
    (net (code "75") (name "Net-(R10-Pad1)") (class "Default")
      (node (ref "R10") (pin "1") (pinfunction "1_1") (pintype "passive"))
      (node (ref "R11") (pin "E") (pinfunction "E_E") (pintype "passive"))
    )
    (net (code "76") (name "PIA-A0") (class "Default")
      (node (ref "CORE-IO") (pin "1") (pinfunction "1_1") (pintype "passive"))
      (node (ref "IC25") (pin "2") (pinfunction "A1_2") (pintype "bidirectional"))
    )
    (net (code "77") (name "PIA-A1") (class "Default")
      (node (ref "CORE-IO") (pin "2") (pinfunction "2_2") (pintype "passive"))
      (node (ref "IC25") (pin "3") (pinfunction "A2_3") (pintype "bidirectional"))
    )
    (net (code "78") (name "PIA-A2") (class "Default")
      (node (ref "CORE-IO") (pin "3") (pinfunction "3_3") (pintype "passive"))
      (node (ref "IC25") (pin "4") (pinfunction "A3_4") (pintype "bidirectional"))
    )
    (net (code "79") (name "PIA-A3") (class "Default")
      (node (ref "CORE-IO") (pin "4") (pinfunction "4_4") (pintype "passive"))
      (node (ref "IC25") (pin "5") (pinfunction "A4_5") (pintype "bidirectional"))
    )
    (net (code "80") (name "PIA-A4") (class "Default")
      (node (ref "CORE-IO") (pin "5") (pinfunction "5_5") (pintype "passive"))
      (node (ref "IC25") (pin "6") (pinfunction "A5_6") (pintype "bidirectional"))
    )
    (net (code "81") (name "PIA-A5") (class "Default")
      (node (ref "CORE-IO") (pin "6") (pinfunction "6_6") (pintype "passive"))
      (node (ref "IC25") (pin "7") (pinfunction "A6_7") (pintype "bidirectional"))
    )
    (net (code "82") (name "PIA-A6") (class "Default")
      (node (ref "CORE-IO") (pin "7") (pinfunction "7_7") (pintype "passive"))
      (node (ref "IC25") (pin "8") (pinfunction "A7_8") (pintype "bidirectional"))
    )
    (net (code "83") (name "PIA-A7") (class "Default")
      (node (ref "CORE-IO") (pin "8") (pinfunction "8_8") (pintype "passive"))
      (node (ref "IC25") (pin "9") (pinfunction "A8_9") (pintype "bidirectional"))
    )
    (net (code "84") (name "PIA-B0") (class "Default")
      (node (ref "CORE-IO") (pin "13") (pinfunction "13_13") (pintype "passive"))
      (node (ref "IC26") (pin "2") (pinfunction "A1_2") (pintype "bidirectional"))
    )
    (net (code "85") (name "PIA-B1") (class "Default")
      (node (ref "CORE-IO") (pin "14") (pinfunction "14_14") (pintype "passive"))
      (node (ref "IC26") (pin "3") (pinfunction "A2_3") (pintype "bidirectional"))
    )
    (net (code "86") (name "PIA-B2") (class "Default")
      (node (ref "CORE-IO") (pin "15") (pinfunction "15_15") (pintype "passive"))
      (node (ref "IC26") (pin "4") (pinfunction "A3_4") (pintype "bidirectional"))
    )
    (net (code "87") (name "PIA-B3") (class "Default")
      (node (ref "CORE-IO") (pin "16") (pinfunction "16_16") (pintype "passive"))
      (node (ref "IC26") (pin "5") (pinfunction "A4_5") (pintype "bidirectional"))
    )
    (net (code "88") (name "PIA-B4") (class "Default")
      (node (ref "CORE-IO") (pin "17") (pinfunction "17_17") (pintype "passive"))
      (node (ref "IC26") (pin "6") (pinfunction "A5_6") (pintype "bidirectional"))
    )
    (net (code "89") (name "PIA-B5") (class "Default")
      (node (ref "CORE-IO") (pin "18") (pinfunction "18_18") (pintype "passive"))
      (node (ref "IC26") (pin "7") (pinfunction "A6_7") (pintype "bidirectional"))
    )
    (net (code "90") (name "PIA-B6") (class "Default")
      (node (ref "CORE-IO") (pin "19") (pinfunction "19_19") (pintype "passive"))
      (node (ref "IC26") (pin "8") (pinfunction "A7_8") (pintype "bidirectional"))
    )
    (net (code "91") (name "PIA-B7") (class "Default")
      (node (ref "CORE-IO") (pin "20") (pinfunction "20_20") (pintype "passive"))
      (node (ref "IC26") (pin "9") (pinfunction "A8_9") (pintype "bidirectional"))
    )
    (net (code "92") (name "RX") (class "Default")
      (node (ref "IC20") (pin "12") (pinfunction "R1OUT_12") (pintype "output"))
      (node (ref "IC21") (pin "2") (pinfunction "RXDATA_2") (pintype "input"))
    )
    (net (code "93") (name "RXD") (class "Default")
      (node (ref "COM") (pin "3") (pinfunction "3_3") (pintype "passive"))
      (node (ref "IC20") (pin "13") (pinfunction "R1IN_13") (pintype "input"))
      (node (ref "RS-232") (pin "3") (pinfunction "3_3") (pintype "passive"))
    )
    (net (code "94") (name "R{slash}~{W}") (class "Default")
      (node (ref "IC17") (pin "34") (pinfunction "R/~{W}_34") (pintype "output"))
      (node (ref "IC21") (pin "13") (pinfunction "R/~{W}_13") (pintype "input"))
      (node (ref "IC22") (pin "27") (pinfunction "~{WE}_27") (pintype "input"))
      (node (ref "IC24") (pin "21") (pinfunction "R/~{W}_21") (pintype "input"))
    )
    (net (code "95") (name "TX") (class "Default")
      (node (ref "IC20") (pin "11") (pinfunction "T1IN_11") (pintype "input"))
      (node (ref "IC21") (pin "6") (pinfunction "TXDATA_6") (pintype "output"))
    )
    (net (code "96") (name "TXD") (class "Default")
      (node (ref "COM") (pin "2") (pinfunction "2_2") (pintype "passive"))
      (node (ref "IC20") (pin "14") (pinfunction "T1OUT_14") (pintype "output"))
      (node (ref "RS-232") (pin "1") (pinfunction "1_1") (pintype "passive"))
    )
    (net (code "97") (name "VCC") (class "Default")
      (node (ref "BYP17") (pin "1") (pinfunction "1_1") (pintype "passive"))
      (node (ref "BYP18") (pin "1") (pinfunction "1_1") (pintype "passive"))
      (node (ref "BYP19") (pin "1") (pinfunction "1_1") (pintype "passive"))
      (node (ref "BYP20") (pin "1") (pinfunction "1_1") (pintype "passive"))
      (node (ref "BYP21") (pin "1") (pinfunction "1_1") (pintype "passive"))
      (node (ref "BYP22") (pin "1") (pinfunction "1_1") (pintype "passive"))
      (node (ref "BYP23") (pin "1") (pinfunction "1_1") (pintype "passive"))
      (node (ref "BYP24") (pin "1") (pinfunction "1_1") (pintype "passive"))
      (node (ref "BYP25") (pin "1") (pinfunction "1_1") (pintype "passive"))
      (node (ref "BYP26") (pin "1") (pinfunction "1_1") (pintype "passive"))
      (node (ref "BYP27") (pin "1") (pinfunction "1_1") (pintype "passive"))
      (node (ref "BYP28") (pin "1") (pinfunction "1_1") (pintype "passive"))
      (node (ref "BYP29") (pin "1") (pinfunction "1_1") (pintype "passive"))
      (node (ref "C10") (pin "1") (pinfunction "1_1") (pintype "passive"))
      (node (ref "CORE-IO") (pin "12") (pinfunction "12_12") (pintype "passive"))
      (node (ref "CORE-IO") (pin "9") (pinfunction "9_9") (pintype "passive"))
      (node (ref "IC17") (pin "35") (pinfunction "VCCSTB_35") (pintype "input"))
      (node (ref "IC17") (pin "36") (pinfunction "RE_36") (pintype "input"))
      (node (ref "IC17") (pin "8") (pinfunction "VCC_8") (pintype "power_in"))
      (node (ref "IC21") (pin "10") (pinfunction "CS1_10") (pintype "input"))
      (node (ref "IC21") (pin "12") (pinfunction "VCC_12") (pintype "power_in"))
      (node (ref "IC21") (pin "8") (pinfunction "CS0_8") (pintype "input"))
      (node (ref "IC22") (pin "28") (pinfunction "VCC_28") (pintype "power_in"))
      (node (ref "IC23") (pin "1") (pinfunction "VPP_1") (pintype "input"))
      (node (ref "IC23") (pin "27") (pinfunction "~{PGM}_27") (pintype "passive"))
      (node (ref "IC23") (pin "28") (pinfunction "VCC_28") (pintype "power_in"))
      (node (ref "IC24") (pin "20") (pinfunction "VCC_20") (pintype "power_in"))
      (node (ref "IC24") (pin "22") (pinfunction "CS0_22") (pintype "input"))
      (node (ref "IC24") (pin "24") (pinfunction "CS1_24") (pintype "input"))
      (node (ref "IC27") (pin "10") (pinfunction "R_10") (pintype "input"))
      (node (ref "IC27") (pin "14") (pinfunction "V+_14") (pintype "power_in"))
      (node (ref "IC27") (pin "4") (pinfunction "R_4") (pintype "input"))
      (node (ref "IC29") (pin "1") (pinfunction "VPP_1") (pintype "input"))
      (node (ref "JP2") (pin "2") (pinfunction "2_2") (pintype "passive"))
      (node (ref "JP4") (pin "2") (pinfunction "2_2") (pintype "passive"))
      (node (ref "R1") (pin "2") (pinfunction "2_2") (pintype "passive"))
      (node (ref "R12") (pin "2") (pinfunction "2_2") (pintype "passive"))
      (node (ref "R14") (pin "2") (pinfunction "2_2") (pintype "passive"))
      (node (ref "R2") (pin "2") (pinfunction "2_2") (pintype "passive"))
      (node (ref "R3") (pin "2") (pinfunction "2_2") (pintype "passive"))
      (node (ref "R5") (pin "2") (pinfunction "2_2") (pintype "passive"))
      (node (ref "R6") (pin "2") (pinfunction "2_2") (pintype "passive"))
      (node (ref "R7") (pin "2") (pinfunction "2_2") (pintype "passive"))
      (node (ref "R8") (pin "2") (pinfunction "2_2") (pintype "passive"))
      (node (ref "R9") (pin "2") (pinfunction "2_2") (pintype "passive"))
    )
    (net (code "98") (name "VMA") (class "Default")
      (node (ref "IC17") (pin "5") (pinfunction "VMA_5") (pintype "output"))
      (node (ref "IC18") (pin "9") (pinfunction "I0_9") (pintype "input"))
    )
    (net (code "99") (name "unconnected-(COM-Pad1)") (class "Default")
      (node (ref "COM") (pin "1") (pinfunction "1_1") (pintype "passive"))
    )
    (net (code "100") (name "unconnected-(COM-Pad9)") (class "Default")
      (node (ref "COM") (pin "9") (pinfunction "9_9") (pintype "passive"))
    )
    (net (code "101") (name "unconnected-(IC17A-BA-Pad7)") (class "Default")
      (node (ref "IC17") (pin "7") (pinfunction "BA_7") (pintype "output"))
    )
    (net (code "102") (name "unconnected-(IC19A-Y0-Pad15)") (class "Default")
      (node (ref "IC19") (pin "15") (pinfunction "Y0_15") (pintype "output"))
    )
    (net (code "103") (name "unconnected-(IC19A-Y1-Pad14)") (class "Default")
      (node (ref "IC19") (pin "14") (pinfunction "Y1_14") (pintype "output"))
    )
    (net (code "104") (name "unconnected-(IC19A-Y2-Pad13)") (class "Default")
      (node (ref "IC19") (pin "13") (pinfunction "Y2_13") (pintype "output"))
    )
    (net (code "105") (name "unconnected-(IC19A-Y3-Pad12)") (class "Default")
      (node (ref "IC19") (pin "12") (pinfunction "Y3_12") (pintype "output"))
    )
    (net (code "106") (name "unconnected-(IC19A-Y4-Pad11)") (class "Default")
      (node (ref "IC19") (pin "11") (pinfunction "Y4_11") (pintype "output"))
    )
    (net (code "107") (name "unconnected-(IC19A-Y5-Pad10)") (class "Default")
      (node (ref "IC19") (pin "10") (pinfunction "Y5_10") (pintype "output"))
    )
    (net (code "108") (name "unconnected-(IC20A-R2OUT-Pad9)") (class "Default")
      (node (ref "IC20") (pin "9") (pinfunction "R2OUT_9") (pintype "output"))
    )
    (net (code "109") (name "unconnected-(IC22-NC-Pad1)") (class "Default")
      (node (ref "IC22") (pin "1") (pinfunction "NC_1") (pintype "no_connect"))
    )
    (net (code "110") (name "unconnected-(IC28A-Y0-Pad4)") (class "Default")
      (node (ref "IC28") (pin "4") (pinfunction "Y0_4") (pintype "output"))
    )
    (net (code "111") (name "unconnected-(IC28B-Y1-Pad11)") (class "Default")
      (node (ref "IC28") (pin "11") (pinfunction "Y1_11") (pintype "output"))
    )
    (net (code "112") (name "unconnected-(IC28B-Y2-Pad10)") (class "Default")
      (node (ref "IC28") (pin "10") (pinfunction "Y2_10") (pintype "output"))
    )
    (net (code "113") (name "~{4-B}") (class "Default")
      (node (ref "IC28") (pin "7") (pinfunction "Y3_7") (pintype "output"))
      (node (ref "IC29") (pin "20") (pinfunction "~{CE}_20") (pintype "input"))
      (node (ref "IC29") (pin "22") (pinfunction "~{OE}_22") (pintype "input"))
    )
    (net (code "114") (name "~{0123}") (class "Default")
      (node (ref "IC19") (pin "5") (pinfunction "G2B_5") (pintype "input"))
      (node (ref "IC22") (pin "20") (pinfunction "~{CS1}_20") (pintype "input"))
      (node (ref "IC22") (pin "22") (pinfunction "~{OE}_22") (pintype "input"))
      (node (ref "IC28") (pin "5") (pinfunction "Y1_5") (pintype "output"))
    )
    (net (code "115") (name "~{CDEF}") (class "Default")
      (node (ref "IC23") (pin "20") (pinfunction "~{CE}_20") (pintype "input"))
      (node (ref "IC23") (pin "22") (pinfunction "~{OE}_22") (pintype "input"))
      (node (ref "IC28") (pin "6") (pinfunction "Y2_6") (pintype "output"))
    )
    (net (code "116") (name "~{EP1}") (class "Default")
      (node (ref "IC28") (pin "2") (pinfunction "A_2") (pintype "input"))
      (node (ref "IC28") (pin "9") (pinfunction "Y3_9") (pintype "output"))
    )
    (net (code "117") (name "~{HLT}") (class "Default")
      (node (ref "IC17") (pin "2") (pinfunction "HALT_2") (pintype "input"))
      (node (ref "R5") (pin "1") (pinfunction "1_1") (pintype "passive"))
    )
    (net (code "118") (name "~{IO-E}") (class "Default")
      (node (ref "IC19") (pin "9") (pinfunction "Y6_9") (pintype "output"))
      (node (ref "IC24") (pin "23") (pinfunction "CS2_23") (pintype "input"))
    )
    (net (code "119") (name "~{IO-F}") (class "Default")
      (node (ref "IC19") (pin "7") (pinfunction "Y7_7") (pintype "output"))
      (node (ref "IC21") (pin "9") (pinfunction "CS2_9") (pintype "input"))
    )
    (net (code "120") (name "~{IRQ}") (class "Default")
      (node (ref "IC17") (pin "4") (pinfunction "IRQ_4") (pintype "input"))
      (node (ref "IC24") (pin "37") (pinfunction "IRQB_37") (pintype "open_collector"))
      (node (ref "IC24") (pin "38") (pinfunction "IRQA_38") (pintype "open_collector"))
      (node (ref "R7") (pin "1") (pinfunction "1_1") (pintype "passive"))
    )
    (net (code "121") (name "~{NMI}") (class "Default")
      (node (ref "IC17") (pin "6") (pinfunction "NMI_6") (pintype "input"))
      (node (ref "IC21") (pin "7") (pinfunction "IRQ_7") (pintype "output"))
      (node (ref "R6") (pin "1") (pinfunction "1_1") (pintype "passive"))
    )
    (net (code "122") (name "~{RST}") (class "Default")
      (node (ref "IC17") (pin "40") (pinfunction "RESET_40") (pintype "input"))
      (node (ref "IC18") (pin "6") (pinfunction "O_6") (pintype "output"))
      (node (ref "IC24") (pin "34") (pinfunction "RESET_34") (pintype "input"))
    )
  )
)
